# TRV_MRF49_U_V1_1_F.net
KiCad netlist of a schematic drawn in EAGLE
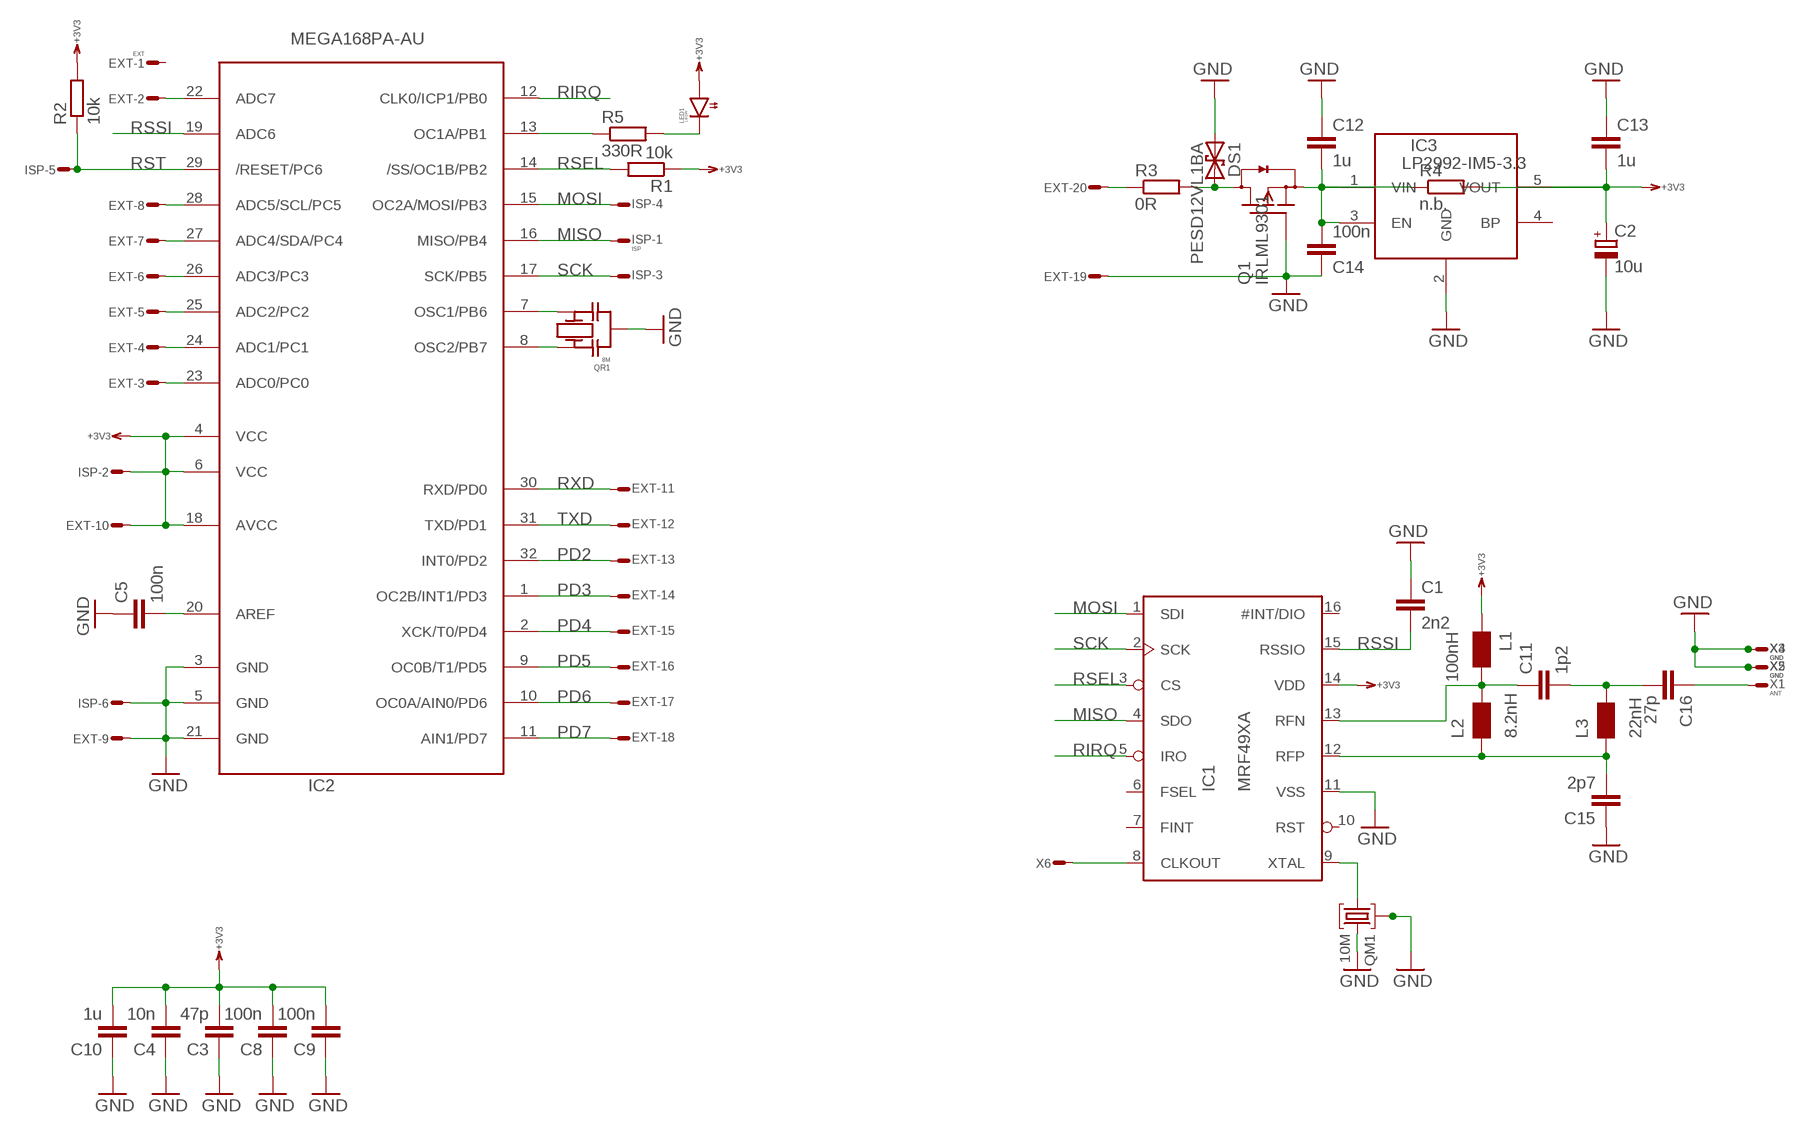
[diagram p0: schematic, sheet 1]

(export (version "E")
  (design (tool "Eeschema 10.0.6"))
  (components
    (comp (ref "C1")
      (value "2n2")
      (footprint "eagle-import:0603")
      (libsource (lib "eagle-import") (part "C0603"))
    )
    (comp (ref "C2")
      (value "10u")
      (footprint "eagle-import:SMC_B")
      (libsource (lib "eagle-import") (part "C_POLSMCB"))
    )
    (comp (ref "C3")
      (value "47p")
      (footprint "eagle-import:0603")
      (libsource (lib "eagle-import") (part "C0603"))
    )
    (comp (ref "C4")
      (value "10n")
      (footprint "eagle-import:0603")
      (libsource (lib "eagle-import") (part "C0603"))
    )
    (comp (ref "C5")
      (value "100n")
      (footprint "eagle-import:0603")
      (libsource (lib "eagle-import") (part "C0603"))
    )
    (comp (ref "C8")
      (value "100n")
      (footprint "eagle-import:0603")
      (libsource (lib "eagle-import") (part "C0603"))
    )
    (comp (ref "C9")
      (value "100n")
      (footprint "eagle-import:0603")
      (libsource (lib "eagle-import") (part "C0603"))
    )
    (comp (ref "C10")
      (value "1u")
      (footprint "eagle-import:0603")
      (libsource (lib "eagle-import") (part "C0603"))
    )
    (comp (ref "C11")
      (value "1p2")
      (footprint "eagle-import:0603")
      (libsource (lib "eagle-import") (part "C0603"))
    )
    (comp (ref "C12")
      (value "1u")
      (footprint "eagle-import:0603")
      (libsource (lib "eagle-import") (part "C0603"))
    )
    (comp (ref "C13")
      (value "1u")
      (footprint "eagle-import:0603")
      (libsource (lib "eagle-import") (part "C0603"))
    )
    (comp (ref "C14")
      (value "100n")
      (footprint "eagle-import:0603")
      (libsource (lib "eagle-import") (part "C0603"))
    )
    (comp (ref "C15")
      (value "2p7")
      (footprint "eagle-import:0603")
      (libsource (lib "eagle-import") (part "C0603"))
    )
    (comp (ref "C16")
      (value "27p")
      (footprint "eagle-import:0603")
      (libsource (lib "eagle-import") (part "C0603"))
    )
    (comp (ref "DS1")
      (value "PESD12VL1BA")
      (footprint "eagle-import:SOD323")
      (libsource (lib "eagle-import") (part "TVS-U323"))
    )
    (comp (ref "EXT")
      (value "EXT")
      (footprint "eagle-import:ML20")
      (libsource (lib "eagle-import") (part "ML20?E"))
    )
    (comp (ref "IC1")
      (value "MRF49XA")
      (footprint "eagle-import:TSSOP16")
      (libsource (lib "eagle-import") (part "MRF49XA"))
    )
    (comp (ref "IC2")
      (value "MEGA168PA-AU")
      (footprint "eagle-import:TQFP32-08")
      (libsource (lib "eagle-import") (part "MEGA168PA"))
    )
    (comp (ref "IC3")
      (value "LP2992-IM5-3.3")
      (footprint "eagle-import:SOT23-5")
      (libsource (lib "eagle-import") (part "LDO"))
    )
    (comp (ref "ISP")
      (value "ISP")
      (footprint "eagle-import:ML6")
      (libsource (lib "eagle-import") (part "ML6E"))
    )
    (comp (ref "L1")
      (value "100nH")
      (footprint "eagle-import:0603")
      (libsource (lib "eagle-import") (part "L0603"))
    )
    (comp (ref "L2")
      (value "8.2nH")
      (footprint "eagle-import:0603")
      (libsource (lib "eagle-import") (part "L0603"))
    )
    (comp (ref "L3")
      (value "22nH")
      (footprint "eagle-import:0603")
      (libsource (lib "eagle-import") (part "L0603"))
    )
    (comp (ref "LED1")
      (value "LEDR")
      (footprint "eagle-import:0603")
      (libsource (lib "eagle-import") (part "LED0603"))
    )
    (comp (ref "Q1")
      (value "IRLML9301")
      (footprint "eagle-import:SOT23")
      (libsource (lib "eagle-import") (part "FET-PDSOT23"))
    )
    (comp (ref "QM1")
      (value "10M")
      (footprint "eagle-import:ABM3C")
      (libsource (lib "eagle-import") (part "QMABM3C"))
    )
    (comp (ref "QR1")
      (value "8M")
      (footprint "eagle-import:CR")
      (libsource (lib "eagle-import") (part "QRCR"))
    )
    (comp (ref "R1")
      (value "10k")
      (footprint "eagle-import:0603")
      (libsource (lib "eagle-import") (part "R0603"))
    )
    (comp (ref "R2")
      (value "10k")
      (footprint "eagle-import:0603")
      (libsource (lib "eagle-import") (part "R0603"))
    )
    (comp (ref "R3")
      (value "0R")
      (footprint "eagle-import:0603")
      (libsource (lib "eagle-import") (part "R0603"))
    )
    (comp (ref "R4")
      (value "n.b.")
      (footprint "eagle-import:0603")
      (libsource (lib "eagle-import") (part "R0603"))
    )
    (comp (ref "R5")
      (value "330R")
      (footprint "eagle-import:0603")
      (libsource (lib "eagle-import") (part "R0603"))
    )
    (comp (ref "X1")
      (value "ANT")
      (footprint "eagle-import:S2.54_1.27")
      (libsource (lib "eagle-import") (part "WIREPADS2.54/1.27"))
    )
    (comp (ref "X2")
      (value "GND")
      (footprint "eagle-import:S2.54_1.27")
      (libsource (lib "eagle-import") (part "WIREPADS2.54/1.27"))
    )
    (comp (ref "X3")
      (value "GND")
      (footprint "eagle-import:S2.54_1.27")
      (libsource (lib "eagle-import") (part "WIREPADS2.54/1.27"))
    )
    (comp (ref "X4")
      (value "GND")
      (footprint "eagle-import:S2.54_1.27")
      (libsource (lib "eagle-import") (part "WIREPADS2.54/1.27"))
    )
    (comp (ref "X5")
      (value "GND")
      (footprint "eagle-import:S2.54_1.27")
      (libsource (lib "eagle-import") (part "WIREPADS2.54/1.27"))
    )
    (comp (ref "X6")
      (value "WIREPADR")
      (footprint "eagle-import:S1.27R")
      (libsource (lib "eagle-import") (part "WIREPADR"))
    )
  )
  (nets
    (net (code "1") (name "+3V3") (class "Default")
      (node (ref "C10") (pin "2") (pinfunction "2_2") (pintype "passive"))
      (node (ref "C13") (pin "2") (pinfunction "2_2") (pintype "passive"))
      (node (ref "C2") (pin "+") (pinfunction "+_+") (pintype "passive"))
      (node (ref "C3") (pin "2") (pinfunction "2_2") (pintype "passive"))
      (node (ref "C4") (pin "2") (pinfunction "2_2") (pintype "passive"))
      (node (ref "C8") (pin "2") (pinfunction "2_2") (pintype "passive"))
      (node (ref "C9") (pin "2") (pinfunction "2_2") (pintype "passive"))
      (node (ref "EXT") (pin "10") (pinfunction "S_10") (pintype "passive"))
      (node (ref "IC1") (pin "14") (pinfunction "VDD_14") (pintype "input"))
      (node (ref "IC2") (pin "18") (pinfunction "AVCC_18") (pintype "bidirectional"))
      (node (ref "IC2") (pin "4") (pinfunction "VCC_4") (pintype "bidirectional"))
      (node (ref "IC2") (pin "6") (pinfunction "VCC_6") (pintype "bidirectional"))
      (node (ref "IC3") (pin "5") (pinfunction "VOUT_5") (pintype "bidirectional"))
      (node (ref "ISP") (pin "2") (pinfunction "S_2") (pintype "passive"))
      (node (ref "L1") (pin "1") (pinfunction "1_1") (pintype "passive"))
      (node (ref "LED1") (pin "1") (pinfunction "A_1") (pintype "bidirectional"))
      (node (ref "R1") (pin "1") (pinfunction "1_1") (pintype "passive"))
      (node (ref "R2") (pin "2") (pinfunction "2_2") (pintype "passive"))
      (node (ref "R4") (pin "2") (pinfunction "2_2") (pintype "passive"))
    )
    (net (code "2") (name "/MISO") (class "Default")
      (node (ref "IC1") (pin "4") (pinfunction "SDO_4") (pintype "output"))
      (node (ref "IC2") (pin "16") (pinfunction "MISO/PB4_16") (pintype "bidirectional"))
      (node (ref "ISP") (pin "1") (pinfunction "S_1") (pintype "passive"))
    )
    (net (code "3") (name "/MOSI") (class "Default")
      (node (ref "IC1") (pin "1") (pinfunction "SDI_1") (pintype "input"))
      (node (ref "IC2") (pin "15") (pinfunction "OC2A/MOSI/PB3_15") (pintype "bidirectional"))
      (node (ref "ISP") (pin "4") (pinfunction "S_4") (pintype "passive"))
    )
    (net (code "4") (name "/PD2") (class "Default")
      (node (ref "EXT") (pin "13") (pinfunction "S_13") (pintype "passive"))
      (node (ref "IC2") (pin "32") (pinfunction "INT0/PD2_32") (pintype "bidirectional"))
    )
    (net (code "5") (name "/PD3") (class "Default")
      (node (ref "EXT") (pin "14") (pinfunction "S_14") (pintype "passive"))
      (node (ref "IC2") (pin "1") (pinfunction "OC2B/INT1/PD3_1") (pintype "bidirectional"))
    )
    (net (code "6") (name "/PD4") (class "Default")
      (node (ref "EXT") (pin "15") (pinfunction "S_15") (pintype "passive"))
      (node (ref "IC2") (pin "2") (pinfunction "XCK/T0/PD4_2") (pintype "bidirectional"))
    )
    (net (code "7") (name "/PD5") (class "Default")
      (node (ref "EXT") (pin "16") (pinfunction "S_16") (pintype "passive"))
      (node (ref "IC2") (pin "9") (pinfunction "OC0B/T1/PD5_9") (pintype "bidirectional"))
    )
    (net (code "8") (name "/PD6") (class "Default")
      (node (ref "EXT") (pin "17") (pinfunction "S_17") (pintype "passive"))
      (node (ref "IC2") (pin "10") (pinfunction "OC0A/AIN0/PD6_10") (pintype "bidirectional"))
    )
    (net (code "9") (name "/PD7") (class "Default")
      (node (ref "EXT") (pin "18") (pinfunction "S_18") (pintype "passive"))
      (node (ref "IC2") (pin "11") (pinfunction "AIN1/PD7_11") (pintype "bidirectional"))
    )
    (net (code "10") (name "/RIRQ") (class "Default")
      (node (ref "IC1") (pin "5") (pinfunction "IRO_5") (pintype "output"))
      (node (ref "IC2") (pin "12") (pinfunction "CLK0/ICP1/PB0_12") (pintype "bidirectional"))
    )
    (net (code "11") (name "/RSEL") (class "Default")
      (node (ref "IC1") (pin "3") (pinfunction "CS_3") (pintype "input"))
      (node (ref "IC2") (pin "14") (pinfunction "/SS/OC1B/PB2_14") (pintype "bidirectional"))
      (node (ref "R1") (pin "2") (pinfunction "2_2") (pintype "passive"))
    )
    (net (code "12") (name "/RSSI") (class "Default")
      (node (ref "C1") (pin "2") (pinfunction "2_2") (pintype "passive"))
      (node (ref "IC1") (pin "15") (pinfunction "RSSIO_15") (pintype "bidirectional"))
      (node (ref "IC2") (pin "19") (pinfunction "ADC6_19") (pintype "bidirectional"))
    )
    (net (code "13") (name "/RST") (class "Default")
      (node (ref "IC2") (pin "29") (pinfunction "/RESET/PC6_29") (pintype "bidirectional"))
      (node (ref "ISP") (pin "5") (pinfunction "S_5") (pintype "passive"))
      (node (ref "R2") (pin "1") (pinfunction "1_1") (pintype "passive"))
    )
    (net (code "14") (name "/RXD") (class "Default")
      (node (ref "EXT") (pin "11") (pinfunction "S_11") (pintype "passive"))
      (node (ref "IC2") (pin "30") (pinfunction "RXD/PD0_30") (pintype "bidirectional"))
    )
    (net (code "15") (name "/SCK") (class "Default")
      (node (ref "IC1") (pin "2") (pinfunction "SCK_2") (pintype "input"))
      (node (ref "IC2") (pin "17") (pinfunction "SCK/PB5_17") (pintype "bidirectional"))
      (node (ref "ISP") (pin "3") (pinfunction "S_3") (pintype "passive"))
    )
    (net (code "16") (name "/TXD") (class "Default")
      (node (ref "EXT") (pin "12") (pinfunction "S_12") (pintype "passive"))
      (node (ref "IC2") (pin "31") (pinfunction "TXD/PD1_31") (pintype "bidirectional"))
    )
    (net (code "17") (name "GND") (class "Default")
      (node (ref "C1") (pin "1") (pinfunction "1_1") (pintype "passive"))
      (node (ref "C10") (pin "1") (pinfunction "1_1") (pintype "passive"))
      (node (ref "C12") (pin "1") (pinfunction "1_1") (pintype "passive"))
      (node (ref "C13") (pin "1") (pinfunction "1_1") (pintype "passive"))
      (node (ref "C14") (pin "1") (pinfunction "1_1") (pintype "passive"))
      (node (ref "C15") (pin "1") (pinfunction "1_1") (pintype "passive"))
      (node (ref "C2") (pin "-") (pinfunction "-_-") (pintype "passive"))
      (node (ref "C3") (pin "1") (pinfunction "1_1") (pintype "passive"))
      (node (ref "C4") (pin "1") (pinfunction "1_1") (pintype "passive"))
      (node (ref "C5") (pin "1") (pinfunction "1_1") (pintype "passive"))
      (node (ref "C8") (pin "1") (pinfunction "1_1") (pintype "passive"))
      (node (ref "C9") (pin "1") (pinfunction "1_1") (pintype "passive"))
      (node (ref "DS1") (pin "A") (pinfunction "1_A") (pintype "passive"))
      (node (ref "EXT") (pin "19") (pinfunction "S_19") (pintype "passive"))
      (node (ref "EXT") (pin "9") (pinfunction "S_9") (pintype "passive"))
      (node (ref "IC1") (pin "11") (pinfunction "VSS_11") (pintype "input"))
      (node (ref "IC2") (pin "21") (pinfunction "GND_21") (pintype "bidirectional"))
      (node (ref "IC2") (pin "3") (pinfunction "GND_3") (pintype "bidirectional"))
      (node (ref "IC2") (pin "5") (pinfunction "GND_5") (pintype "bidirectional"))
      (node (ref "IC3") (pin "2") (pinfunction "GND_2") (pintype "bidirectional"))
      (node (ref "ISP") (pin "6") (pinfunction "S_6") (pintype "passive"))
      (node (ref "Q1") (pin "1") (pinfunction "G_1") (pintype "passive"))
      (node (ref "QM1") (pin "P$2") (pinfunction "M1_P$2") (pintype "passive"))
      (node (ref "QM1") (pin "P$3") (pinfunction "2_P$3") (pintype "passive"))
      (node (ref "QM1") (pin "P$4") (pinfunction "M2_P$4") (pintype "passive"))
      (node (ref "QR1") (pin "M") (pinfunction "M_M") (pintype "passive"))
      (node (ref "X2") (pin "1") (pinfunction "S_1") (pintype "passive"))
      (node (ref "X3") (pin "1") (pinfunction "S_1") (pintype "passive"))
      (node (ref "X4") (pin "1") (pinfunction "S_1") (pintype "passive"))
      (node (ref "X5") (pin "1") (pinfunction "S_1") (pintype "passive"))
    )
    (net (code "18") (name "Net-(C11-Pad2)") (class "Default")
      (node (ref "C11") (pin "2") (pinfunction "2_2") (pintype "passive"))
      (node (ref "C16") (pin "2") (pinfunction "2_2") (pintype "passive"))
      (node (ref "L3") (pin "2") (pinfunction "2_2") (pintype "passive"))
    )
    (net (code "19") (name "Net-(DS1-2)") (class "Default")
      (node (ref "DS1") (pin "C") (pinfunction "2_C") (pintype "passive"))
      (node (ref "Q1") (pin "3") (pinfunction "D_3") (pintype "passive"))
      (node (ref "R3") (pin "2") (pinfunction "2_2") (pintype "passive"))
    )
    (net (code "20") (name "Net-(EXTL-S)") (class "Default")
      (node (ref "EXT") (pin "2") (pinfunction "S_2") (pintype "passive"))
      (node (ref "IC2") (pin "22") (pinfunction "ADC7_22") (pintype "bidirectional"))
    )
    (net (code "21") (name "Net-(EXTM-S)") (class "Default")
      (node (ref "EXT") (pin "20") (pinfunction "S_20") (pintype "passive"))
      (node (ref "R3") (pin "1") (pinfunction "1_1") (pintype "passive"))
    )
    (net (code "22") (name "Net-(EXTN-S)") (class "Default")
      (node (ref "EXT") (pin "3") (pinfunction "S_3") (pintype "passive"))
      (node (ref "IC2") (pin "23") (pinfunction "ADC0/PC0_23") (pintype "bidirectional"))
    )
    (net (code "23") (name "Net-(EXTO-S)") (class "Default")
      (node (ref "EXT") (pin "4") (pinfunction "S_4") (pintype "passive"))
      (node (ref "IC2") (pin "24") (pinfunction "ADC1/PC1_24") (pintype "bidirectional"))
    )
    (net (code "24") (name "Net-(EXTP-S)") (class "Default")
      (node (ref "EXT") (pin "5") (pinfunction "S_5") (pintype "passive"))
      (node (ref "IC2") (pin "25") (pinfunction "ADC2/PC2_25") (pintype "bidirectional"))
    )
    (net (code "25") (name "Net-(EXTQ-S)") (class "Default")
      (node (ref "EXT") (pin "6") (pinfunction "S_6") (pintype "passive"))
      (node (ref "IC2") (pin "26") (pinfunction "ADC3/PC3_26") (pintype "bidirectional"))
    )
    (net (code "26") (name "Net-(EXTR-S)") (class "Default")
      (node (ref "EXT") (pin "7") (pinfunction "S_7") (pintype "passive"))
      (node (ref "IC2") (pin "27") (pinfunction "ADC4/SDA/PC4_27") (pintype "bidirectional"))
    )
    (net (code "27") (name "Net-(EXTS-S)") (class "Default")
      (node (ref "EXT") (pin "8") (pinfunction "S_8") (pintype "passive"))
      (node (ref "IC2") (pin "28") (pinfunction "ADC5/SCL/PC5_28") (pintype "bidirectional"))
    )
    (net (code "28") (name "Net-(IC1-CLKOUT)") (class "Default")
      (node (ref "IC1") (pin "8") (pinfunction "CLKOUT_8") (pintype "output"))
      (node (ref "X6") (pin "1") (pinfunction "S_1") (pintype "passive"))
    )
    (net (code "29") (name "Net-(IC1-RFN)") (class "Default")
      (node (ref "C11") (pin "1") (pinfunction "1_1") (pintype "passive"))
      (node (ref "IC1") (pin "13") (pinfunction "RFN_13") (pintype "bidirectional"))
      (node (ref "L1") (pin "2") (pinfunction "2_2") (pintype "passive"))
      (node (ref "L2") (pin "2") (pinfunction "2_2") (pintype "passive"))
    )
    (net (code "30") (name "Net-(IC1-RFP)") (class "Default")
      (node (ref "C15") (pin "2") (pinfunction "2_2") (pintype "passive"))
      (node (ref "IC1") (pin "12") (pinfunction "RFP_12") (pintype "bidirectional"))
      (node (ref "L2") (pin "1") (pinfunction "1_1") (pintype "passive"))
      (node (ref "L3") (pin "1") (pinfunction "1_1") (pintype "passive"))
    )
    (net (code "31") (name "Net-(IC1-XTAL)") (class "Default")
      (node (ref "IC1") (pin "9") (pinfunction "XTAL_9") (pintype "input"))
      (node (ref "QM1") (pin "P$1") (pinfunction "1_P$1") (pintype "passive"))
    )
    (net (code "32") (name "Net-(IC2-AREF)") (class "Default")
      (node (ref "C5") (pin "2") (pinfunction "2_2") (pintype "passive"))
      (node (ref "IC2") (pin "20") (pinfunction "AREF_20") (pintype "bidirectional"))
    )
    (net (code "33") (name "Net-(IC2-OC1A{slash}PB1)") (class "Default")
      (node (ref "IC2") (pin "13") (pinfunction "OC1A/PB1_13") (pintype "bidirectional"))
      (node (ref "R5") (pin "1") (pinfunction "1_1") (pintype "passive"))
    )
    (net (code "34") (name "Net-(IC2-OSC1{slash}PB6)") (class "Default")
      (node (ref "IC2") (pin "7") (pinfunction "OSC1/PB6_7") (pintype "bidirectional"))
      (node (ref "QR1") (pin "2") (pinfunction "2_2") (pintype "passive"))
    )
    (net (code "35") (name "Net-(IC2-OSC2{slash}PB7)") (class "Default")
      (node (ref "IC2") (pin "8") (pinfunction "OSC2/PB7_8") (pintype "bidirectional"))
      (node (ref "QR1") (pin "1") (pinfunction "1_1") (pintype "passive"))
    )
    (net (code "36") (name "Net-(IC3-EN)") (class "Default")
      (node (ref "C12") (pin "2") (pinfunction "2_2") (pintype "passive"))
      (node (ref "C14") (pin "2") (pinfunction "2_2") (pintype "passive"))
      (node (ref "IC3") (pin "1") (pinfunction "VIN_1") (pintype "bidirectional"))
      (node (ref "IC3") (pin "3") (pinfunction "EN_3") (pintype "bidirectional"))
      (node (ref "Q1") (pin "2") (pinfunction "S_2") (pintype "passive"))
      (node (ref "R4") (pin "1") (pinfunction "1_1") (pintype "passive"))
    )
    (net (code "37") (name "Net-(LED1-C)") (class "Default")
      (node (ref "LED1") (pin "2") (pinfunction "C_2") (pintype "bidirectional"))
      (node (ref "R5") (pin "2") (pinfunction "2_2") (pintype "passive"))
    )
    (net (code "38") (name "Net-(X1-S)") (class "Default")
      (node (ref "C16") (pin "1") (pinfunction "1_1") (pintype "passive"))
      (node (ref "X1") (pin "1") (pinfunction "S_1") (pintype "passive"))
    )
    (net (code "39") (name "unconnected-(EXTA-S-Pad1)") (class "Default")
      (node (ref "EXT") (pin "1") (pinfunction "S_1") (pintype "passive"))
    )
    (net (code "40") (name "unconnected-(IC1-#INT{slash}DIO-Pad16)") (class "Default")
      (node (ref "IC1") (pin "16") (pinfunction "#INT/DIO_16") (pintype "bidirectional"))
    )
    (net (code "41") (name "unconnected-(IC1-FINT-Pad7)") (class "Default")
      (node (ref "IC1") (pin "7") (pinfunction "FINT_7") (pintype "bidirectional"))
    )
    (net (code "42") (name "unconnected-(IC1-FSEL-Pad6)") (class "Default")
      (node (ref "IC1") (pin "6") (pinfunction "FSEL_6") (pintype "bidirectional"))
    )
    (net (code "43") (name "unconnected-(IC1-RST-Pad10)") (class "Default")
      (node (ref "IC1") (pin "10") (pinfunction "RST_10") (pintype "bidirectional"))
    )
    (net (code "44") (name "unconnected-(IC3-BP-Pad4)") (class "Default")
      (node (ref "IC3") (pin "4") (pinfunction "BP_4") (pintype "bidirectional"))
    )
  )
)
